# transmitter.net
KiCad netlist of a schematic drawn in EAGLE
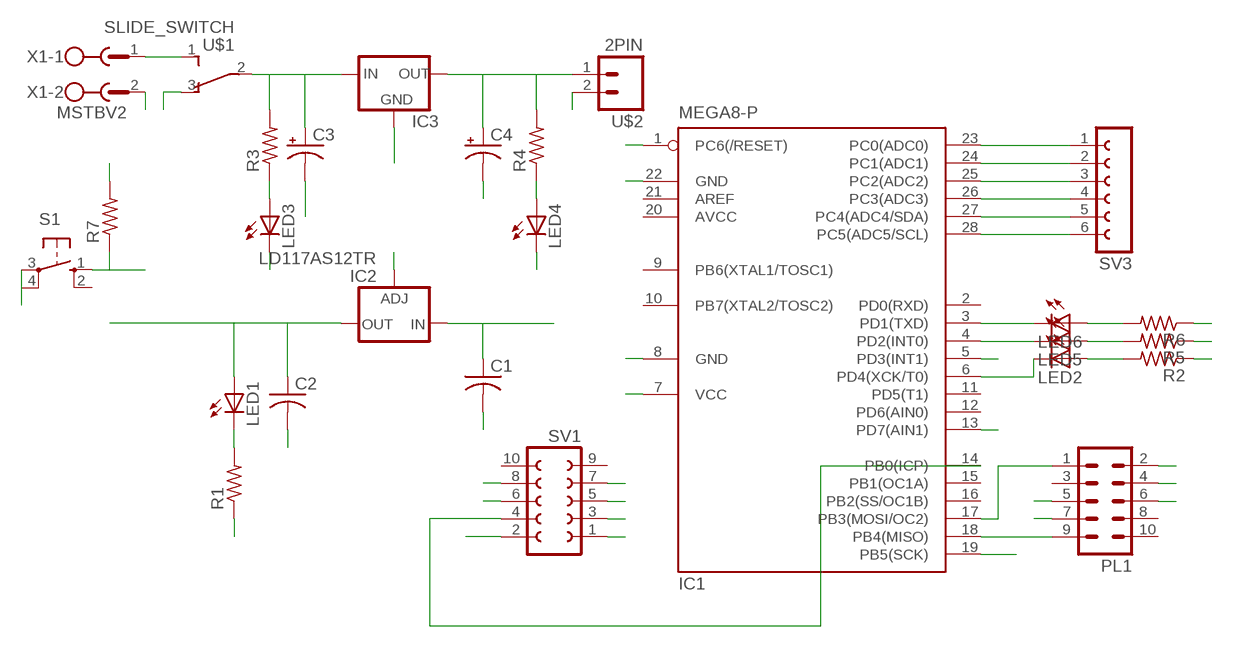
[diagram p0: schematic, sheet 1]

(export (version "E")
  (design (tool "Eeschema 10.0.6"))
  (components
    (comp (ref "C1")
      (value "C-US025-025X050")
      (footprint "eagle-import:C025-025X050")
      (libsource (lib "eagle-import") (part "C-US025-025X050"))
    )
    (comp (ref "C2")
      (value "C-US025-025X050")
      (footprint "eagle-import:C025-025X050")
      (libsource (lib "eagle-import") (part "C-US025-025X050"))
    )
    (comp (ref "C3")
      (value "CPOL-USE2.5-6")
      (footprint "eagle-import:E2,5-6")
      (libsource (lib "eagle-import") (part "CPOL-USE2.5-6"))
    )
    (comp (ref "C4")
      (value "CPOL-USE2.5-6")
      (footprint "eagle-import:E2,5-6")
      (libsource (lib "eagle-import") (part "CPOL-USE2.5-6"))
    )
    (comp (ref "IC1")
      (value "MEGA8-P")
      (footprint "eagle-import:DIL28-3")
      (libsource (lib "eagle-import") (part "MEGA8-P"))
    )
    (comp (ref "IC2")
      (value "LD117AS12TR")
      (footprint "eagle-import:SOT223")
      (libsource (lib "eagle-import") (part "LD117A?S12TR"))
    )
    (comp (ref "IC3")
      (value "78XXS")
      (footprint "eagle-import:78XXS")
      (libsource (lib "eagle-import") (part "78XXS"))
    )
    (comp (ref "LED1")
      (value "LED3MM")
      (footprint "eagle-import:LED3MM")
      (libsource (lib "eagle-import") (part "LED3MM"))
    )
    (comp (ref "LED2")
      (value "LED3MM")
      (footprint "eagle-import:LED3MM")
      (libsource (lib "eagle-import") (part "LED3MM"))
    )
    (comp (ref "LED3")
      (value "LED3MM")
      (footprint "eagle-import:LED3MM")
      (libsource (lib "eagle-import") (part "LED3MM"))
    )
    (comp (ref "LED4")
      (value "LED3MM")
      (footprint "eagle-import:LED3MM")
      (libsource (lib "eagle-import") (part "LED3MM"))
    )
    (comp (ref "LED5")
      (value "LED3MM")
      (footprint "eagle-import:LED3MM")
      (libsource (lib "eagle-import") (part "LED3MM"))
    )
    (comp (ref "LED6")
      (value "LED3MM")
      (footprint "eagle-import:LED3MM")
      (libsource (lib "eagle-import") (part "LED3MM"))
    )
    (comp (ref "PL1")
      (value "ML10")
      (footprint "eagle-import:ML10")
      (libsource (lib "eagle-import") (part "ML10"))
    )
    (comp (ref "R1")
      (value "R-US_0207/10")
      (footprint "eagle-import:0207_10")
      (libsource (lib "eagle-import") (part "R-US_0207/10"))
    )
    (comp (ref "R2")
      (value "R-US_0207/10")
      (footprint "eagle-import:0207_10")
      (libsource (lib "eagle-import") (part "R-US_0207/10"))
    )
    (comp (ref "R3")
      (value "R-US_0207/10")
      (footprint "eagle-import:0207_10")
      (libsource (lib "eagle-import") (part "R-US_0207/10"))
    )
    (comp (ref "R4")
      (value "R-US_0207/10")
      (footprint "eagle-import:0207_10")
      (libsource (lib "eagle-import") (part "R-US_0207/10"))
    )
    (comp (ref "R5")
      (value "R-US_0207/10")
      (footprint "eagle-import:0207_10")
      (libsource (lib "eagle-import") (part "R-US_0207/10"))
    )
    (comp (ref "R6")
      (value "R-US_0207/10")
      (footprint "eagle-import:0207_10")
      (libsource (lib "eagle-import") (part "R-US_0207/10"))
    )
    (comp (ref "R7")
      (value "R-US_0207/10")
      (footprint "eagle-import:0207_10")
      (libsource (lib "eagle-import") (part "R-US_0207/10"))
    )
    (comp (ref "S1")
      (value "10-XX")
      (footprint "eagle-import:B3F-10XX")
      (fields (field (name "MPN") "B3F-1000"))
      (libsource (lib "eagle-import") (part "10-XX"))
    )
    (comp (ref "SV1")
      (value "FE05-2")
      (footprint "eagle-import:FE05-2")
      (libsource (lib "eagle-import") (part "FE05-2"))
    )
    (comp (ref "SV3")
      (value "FE06-1")
      (footprint "eagle-import:FE06")
      (libsource (lib "eagle-import") (part "FE06-1"))
    )
    (comp (ref "U$1")
      (value "SLIDE_SWITCH")
      (footprint "eagle-import:SPDT")
      (libsource (lib "eagle-import") (part "SLIDE_SWITCH"))
    )
    (comp (ref "U$2")
      (value "2PIN")
      (footprint "eagle-import:2PIN")
      (libsource (lib "eagle-import") (part "2PIN"))
    )
    (comp (ref "X1")
      (value "MSTBV2")
      (footprint "eagle-import:MSTBV2")
      (fields (field (name "MPN") "MSTBV 2,5/2-GF-5.08"))
      (libsource (lib "eagle-import") (part "MSTBV2"))
    )
  )
  (nets
    (net (code "1") (name "/AVCC") (class "Default")
      (node (ref "IC1") (pin "20") (pinfunction "AVCC_20") (pintype "power_in"))
    )
    (net (code "2") (name "/CE") (class "Default")
      (node (ref "IC1") (pin "13") (pinfunction "PD7(AIN1)_13") (pintype "bidirectional"))
      (node (ref "SV1") (pin "3") (pinfunction "3_3") (pintype "passive"))
    )
    (net (code "3") (name "/GND") (class "Default")
      (node (ref "C1") (pin "2") (pinfunction "2_2") (pintype "passive"))
      (node (ref "C2") (pin "2") (pinfunction "2_2") (pintype "passive"))
      (node (ref "C3") (pin "-") (pinfunction "-_-") (pintype "passive"))
      (node (ref "C4") (pin "-") (pinfunction "-_-") (pintype "passive"))
      (node (ref "IC1") (pin "22") (pinfunction "GND_22") (pintype "power_in"))
      (node (ref "IC1") (pin "8") (pinfunction "GND_8") (pintype "power_in"))
      (node (ref "IC2") (pin "1") (pinfunction "ADJ_1") (pintype "input"))
      (node (ref "IC3") (pin "GND") (pinfunction "GND_GND") (pintype "input"))
      (node (ref "LED3") (pin "K") (pinfunction "C_K") (pintype "passive"))
      (node (ref "LED4") (pin "K") (pinfunction "C_K") (pintype "passive"))
      (node (ref "PL1") (pin "4") (pinfunction "4_4") (pintype "passive"))
      (node (ref "PL1") (pin "6") (pinfunction "6_6") (pintype "passive"))
      (node (ref "R1") (pin "1") (pinfunction "1_1") (pintype "passive"))
      (node (ref "S1") (pin "3") (pinfunction "P_3") (pintype "passive"))
      (node (ref "SV1") (pin "1") (pinfunction "1_1") (pintype "passive"))
      (node (ref "U$1") (pin "3") (pinfunction "NC_3") (pintype "passive"))
      (node (ref "U$2") (pin "2") (pinfunction "2_2") (pintype "passive"))
      (node (ref "X1") (pin "2") (pinfunction "1_2") (pintype "passive"))
    )
    (net (code "4") (name "/IRQ") (class "Default")
      (node (ref "IC1") (pin "5") (pinfunction "PD3(INT1)_5") (pintype "bidirectional"))
      (node (ref "SV1") (pin "8") (pinfunction "8_8") (pintype "passive"))
    )
    (net (code "5") (name "/MISO") (class "Default")
      (node (ref "IC1") (pin "18") (pinfunction "PB4(MISO)_18") (pintype "bidirectional"))
      (node (ref "PL1") (pin "9") (pinfunction "9_9") (pintype "passive"))
      (node (ref "SV1") (pin "7") (pinfunction "7_7") (pintype "passive"))
    )
    (net (code "6") (name "/MOSI") (class "Default")
      (node (ref "IC1") (pin "17") (pinfunction "PB3(MOSI/OC2)_17") (pintype "bidirectional"))
      (node (ref "PL1") (pin "1") (pinfunction "1_1") (pintype "passive"))
      (node (ref "SV1") (pin "6") (pinfunction "6_6") (pintype "passive"))
    )
    (net (code "7") (name "/RST") (class "Default")
      (node (ref "IC1") (pin "1") (pinfunction "PC6(/RESET)_1") (pintype "bidirectional"))
      (node (ref "PL1") (pin "5") (pinfunction "5_5") (pintype "passive"))
      (node (ref "R7") (pin "1") (pinfunction "1_1") (pintype "passive"))
      (node (ref "S1") (pin "1") (pinfunction "S_1") (pintype "passive"))
    )
    (net (code "8") (name "/SCK") (class "Default")
      (node (ref "IC1") (pin "19") (pinfunction "PB5(SCK)_19") (pintype "bidirectional"))
      (node (ref "PL1") (pin "7") (pinfunction "7_7") (pintype "passive"))
      (node (ref "SV1") (pin "5") (pinfunction "5_5") (pintype "passive"))
    )
    (net (code "9") (name "/VCC") (class "Default")
      (node (ref "C1") (pin "1") (pinfunction "1_1") (pintype "passive"))
      (node (ref "C4") (pin "+") (pinfunction "+_+") (pintype "passive"))
      (node (ref "IC1") (pin "7") (pinfunction "VCC_7") (pintype "power_in"))
      (node (ref "IC2") (pin "3") (pinfunction "IN_3") (pintype "input"))
      (node (ref "IC3") (pin "OUT") (pinfunction "OUT_OUT") (pintype "passive"))
      (node (ref "PL1") (pin "2") (pinfunction "2_2") (pintype "passive"))
      (node (ref "R2") (pin "1") (pinfunction "1_1") (pintype "passive"))
      (node (ref "R4") (pin "2") (pinfunction "2_2") (pintype "passive"))
      (node (ref "R7") (pin "2") (pinfunction "2_2") (pintype "passive"))
      (node (ref "U$2") (pin "1") (pinfunction "1_1") (pintype "passive"))
    )
    (net (code "10") (name "/VCC3.3") (class "Default")
      (node (ref "C2") (pin "1") (pinfunction "1_1") (pintype "passive"))
      (node (ref "IC2") (pin "4") (pinfunction "OUT_4") (pintype "passive"))
      (node (ref "LED1") (pin "A") (pinfunction "A_A") (pintype "passive"))
      (node (ref "SV1") (pin "2") (pinfunction "2_2") (pintype "passive"))
    )
    (net (code "11") (name "Net-(IC1-PB0(ICP))") (class "Default")
      (node (ref "IC1") (pin "14") (pinfunction "PB0(ICP)_14") (pintype "bidirectional"))
      (node (ref "SV1") (pin "4") (pinfunction "4_4") (pintype "passive"))
    )
    (net (code "12") (name "Net-(IC1-PC0(ADC0))") (class "Default")
      (node (ref "IC1") (pin "23") (pinfunction "PC0(ADC0)_23") (pintype "bidirectional"))
      (node (ref "SV3") (pin "1") (pinfunction "1_1") (pintype "passive"))
    )
    (net (code "13") (name "Net-(IC1-PC1(ADC1))") (class "Default")
      (node (ref "IC1") (pin "24") (pinfunction "PC1(ADC1)_24") (pintype "bidirectional"))
      (node (ref "SV3") (pin "2") (pinfunction "2_2") (pintype "passive"))
    )
    (net (code "14") (name "Net-(IC1-PC2(ADC2))") (class "Default")
      (node (ref "IC1") (pin "25") (pinfunction "PC2(ADC2)_25") (pintype "bidirectional"))
      (node (ref "SV3") (pin "3") (pinfunction "3_3") (pintype "passive"))
    )
    (net (code "15") (name "Net-(IC1-PC3(ADC3))") (class "Default")
      (node (ref "IC1") (pin "26") (pinfunction "PC3(ADC3)_26") (pintype "bidirectional"))
      (node (ref "SV3") (pin "4") (pinfunction "4_4") (pintype "passive"))
    )
    (net (code "16") (name "Net-(IC1-PC4(ADC4{slash}SDA))") (class "Default")
      (node (ref "IC1") (pin "27") (pinfunction "PC4(ADC4/SDA)_27") (pintype "bidirectional"))
      (node (ref "SV3") (pin "5") (pinfunction "5_5") (pintype "passive"))
    )
    (net (code "17") (name "Net-(IC1-PC5(ADC5{slash}SCL))") (class "Default")
      (node (ref "IC1") (pin "28") (pinfunction "PC5(ADC5/SCL)_28") (pintype "bidirectional"))
      (node (ref "SV3") (pin "6") (pinfunction "6_6") (pintype "passive"))
    )
    (net (code "18") (name "Net-(IC1-PD1(TXD))") (class "Default")
      (node (ref "IC1") (pin "3") (pinfunction "PD1(TXD)_3") (pintype "bidirectional"))
      (node (ref "LED6") (pin "K") (pinfunction "C_K") (pintype "passive"))
    )
    (net (code "19") (name "Net-(IC1-PD2(INT0))") (class "Default")
      (node (ref "IC1") (pin "4") (pinfunction "PD2(INT0)_4") (pintype "bidirectional"))
      (node (ref "LED5") (pin "K") (pinfunction "C_K") (pintype "passive"))
    )
    (net (code "20") (name "Net-(IC1-PD4(XCK{slash}T0))") (class "Default")
      (node (ref "IC1") (pin "6") (pinfunction "PD4(XCK/T0)_6") (pintype "bidirectional"))
      (node (ref "LED2") (pin "K") (pinfunction "C_K") (pintype "passive"))
    )
    (net (code "21") (name "Net-(LED1-C)") (class "Default")
      (node (ref "LED1") (pin "K") (pinfunction "C_K") (pintype "passive"))
      (node (ref "R1") (pin "2") (pinfunction "2_2") (pintype "passive"))
    )
    (net (code "22") (name "Net-(LED2-PadA)") (class "Default")
      (node (ref "LED2") (pin "A") (pinfunction "A_A") (pintype "passive"))
      (node (ref "R2") (pin "2") (pinfunction "2_2") (pintype "passive"))
    )
    (net (code "23") (name "Net-(LED3-PadA)") (class "Default")
      (node (ref "LED3") (pin "A") (pinfunction "A_A") (pintype "passive"))
      (node (ref "R3") (pin "1") (pinfunction "1_1") (pintype "passive"))
    )
    (net (code "24") (name "Net-(LED4-PadA)") (class "Default")
      (node (ref "LED4") (pin "A") (pinfunction "A_A") (pintype "passive"))
      (node (ref "R4") (pin "1") (pinfunction "1_1") (pintype "passive"))
    )
    (net (code "25") (name "Net-(LED5-PadA)") (class "Default")
      (node (ref "LED5") (pin "A") (pinfunction "A_A") (pintype "passive"))
      (node (ref "R5") (pin "2") (pinfunction "2_2") (pintype "passive"))
    )
    (net (code "26") (name "Net-(LED6-PadA)") (class "Default")
      (node (ref "LED6") (pin "A") (pinfunction "A_A") (pintype "passive"))
      (node (ref "R6") (pin "2") (pinfunction "2_2") (pintype "passive"))
    )
    (net (code "27") (name "Net-(U$1-NO)") (class "Default")
      (node (ref "U$1") (pin "1") (pinfunction "NO_1") (pintype "passive"))
      (node (ref "X1") (pin "1") (pinfunction "1_1") (pintype "passive"))
    )
    (net (code "28") (name "Net-(U$1-P)") (class "Default")
      (node (ref "C3") (pin "+") (pinfunction "+_+") (pintype "passive"))
      (node (ref "IC3") (pin "IN") (pinfunction "IN_IN") (pintype "input"))
      (node (ref "R3") (pin "2") (pinfunction "2_2") (pintype "passive"))
      (node (ref "U$1") (pin "2") (pinfunction "P_2") (pintype "passive"))
    )
    (net (code "29") (name "unconnected-(IC1-AREF-Pad21)") (class "Default")
      (node (ref "IC1") (pin "21") (pinfunction "AREF_21") (pintype "passive"))
    )
    (net (code "30") (name "unconnected-(IC1-PB1(OC1A)-Pad15)") (class "Default")
      (node (ref "IC1") (pin "15") (pinfunction "PB1(OC1A)_15") (pintype "bidirectional"))
    )
    (net (code "31") (name "unconnected-(IC1-PB2(SS{slash}OC1B)-Pad16)") (class "Default")
      (node (ref "IC1") (pin "16") (pinfunction "PB2(SS/OC1B)_16") (pintype "bidirectional"))
    )
    (net (code "32") (name "unconnected-(IC1-PB6(XTAL1{slash}TOSC1)-Pad9)") (class "Default")
      (node (ref "IC1") (pin "9") (pinfunction "PB6(XTAL1/TOSC1)_9") (pintype "bidirectional"))
    )
    (net (code "33") (name "unconnected-(IC1-PB7(XTAL2{slash}TOSC2)-Pad10)") (class "Default")
      (node (ref "IC1") (pin "10") (pinfunction "PB7(XTAL2/TOSC2)_10") (pintype "bidirectional"))
    )
    (net (code "34") (name "unconnected-(IC1-PD0(RXD)-Pad2)") (class "Default")
      (node (ref "IC1") (pin "2") (pinfunction "PD0(RXD)_2") (pintype "bidirectional"))
    )
    (net (code "35") (name "unconnected-(IC1-PD5(T1)-Pad11)") (class "Default")
      (node (ref "IC1") (pin "11") (pinfunction "PD5(T1)_11") (pintype "bidirectional"))
    )
    (net (code "36") (name "unconnected-(IC1-PD6(AIN0)-Pad12)") (class "Default")
      (node (ref "IC1") (pin "12") (pinfunction "PD6(AIN0)_12") (pintype "bidirectional"))
    )
    (net (code "37") (name "unconnected-(PL1-Pad3)") (class "Default")
      (node (ref "PL1") (pin "3") (pinfunction "3_3") (pintype "passive"))
    )
    (net (code "38") (name "unconnected-(PL1-Pad8)") (class "Default")
      (node (ref "PL1") (pin "8") (pinfunction "8_8") (pintype "passive"))
    )
    (net (code "39") (name "unconnected-(PL1-Pad10)") (class "Default")
      (node (ref "PL1") (pin "10") (pinfunction "10_10") (pintype "passive"))
    )
    (net (code "40") (name "unconnected-(R5-Pad1)") (class "Default")
      (node (ref "R5") (pin "1") (pinfunction "1_1") (pintype "passive"))
    )
    (net (code "41") (name "unconnected-(R6-Pad1)") (class "Default")
      (node (ref "R6") (pin "1") (pinfunction "1_1") (pintype "passive"))
    )
    (net (code "42") (name "unconnected-(S1-P1-Pad4)") (class "Default")
      (node (ref "S1") (pin "4") (pinfunction "P1_4") (pintype "passive"))
    )
    (net (code "43") (name "unconnected-(S1-S1-Pad2)") (class "Default")
      (node (ref "S1") (pin "2") (pinfunction "S1_2") (pintype "passive"))
    )
    (net (code "44") (name "unconnected-(SV1-Pad9)") (class "Default")
      (node (ref "SV1") (pin "9") (pinfunction "9_9") (pintype "passive"))
    )
    (net (code "45") (name "unconnected-(SV1-Pad10)") (class "Default")
      (node (ref "SV1") (pin "10") (pinfunction "10_10") (pintype "passive"))
    )
  )
)
